# eeprom.net
KiCad netlist of a schematic drawn in Altium Designer
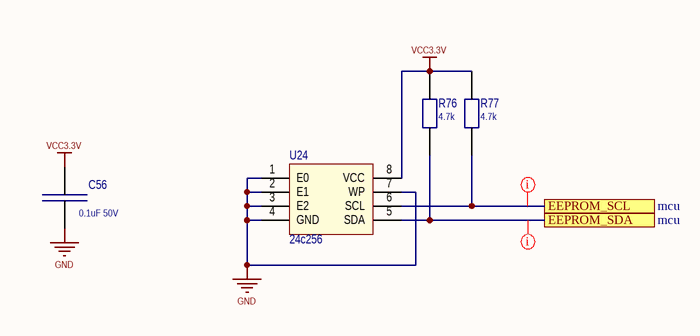
[diagram p0: eeprom.SchDoc]

(export (version "E")
  (design (tool "Eeschema 10.0.6"))
  (components
    (comp (ref "C56")
      (value "0.1uF 50V")
      (footprint "C_0603")
      (description "Capacitor")
      (fields (field (name "PART") "CC0603KPX7R9BB104"))
      (libsource (lib "AX_Altium_v2.3") (part "C0603"))
    )
    (comp (ref "R76")
      (value "4.7k")
      (footprint "R_0603")
      (description "Resistor")
      (fields (field (name "PART") "RC0603FR-074K7L"))
      (libsource (lib "resistors") (part "RES_SMD"))
    )
    (comp (ref "R77")
      (value "4.7k")
      (footprint "R_0603")
      (description "Resistor")
      (fields (field (name "PART") "RC0603FR-074K7L"))
      (libsource (lib "resistors") (part "RES_SMD"))
    )
    (comp (ref "U24")
      (value "24c256")
      (footprint "SO-8_M")
      (description "256-Kbit I2C-compatible Serial EEPROM")
      (fields (field (name "PART") "AT24C256C"))
      (libsource (lib "discret_ic") (part "24c256"))
    )
  )
  (nets
    (net (code "1") (name "/EEPROM_SCL") (class "Default")
      (node (ref "R77") (pin "1") (pinfunction "1_1") (pintype "passive"))
      (node (ref "U24") (pin "6") (pinfunction "SCL_6") (pintype "passive"))
    )
    (net (code "2") (name "/EEPROM_SDA") (class "Default")
      (node (ref "R76") (pin "1") (pinfunction "1_1") (pintype "passive"))
      (node (ref "U24") (pin "5") (pinfunction "SDA_5") (pintype "passive"))
    )
    (net (code "3") (name "GND") (class "Default")
      (node (ref "C56") (pin "1") (pinfunction "1_1") (pintype "passive"))
      (node (ref "U24") (pin "1") (pinfunction "E0_1") (pintype "passive"))
      (node (ref "U24") (pin "2") (pinfunction "E1_2") (pintype "passive"))
      (node (ref "U24") (pin "3") (pinfunction "E2_3") (pintype "passive"))
      (node (ref "U24") (pin "4") (pinfunction "GND_4") (pintype "passive"))
      (node (ref "U24") (pin "7") (pinfunction "WP_7") (pintype "passive"))
    )
    (net (code "4") (name "VCC3.3V") (class "Default")
      (node (ref "C56") (pin "2") (pinfunction "2_2") (pintype "passive"))
      (node (ref "R76") (pin "2") (pinfunction "2_2") (pintype "passive"))
      (node (ref "R77") (pin "2") (pinfunction "2_2") (pintype "passive"))
      (node (ref "U24") (pin "8") (pinfunction "VCC_8") (pintype "passive"))
    )
  )
)
